# LSM9DS1.net
KiCad netlist of a schematic drawn in Altium Designer
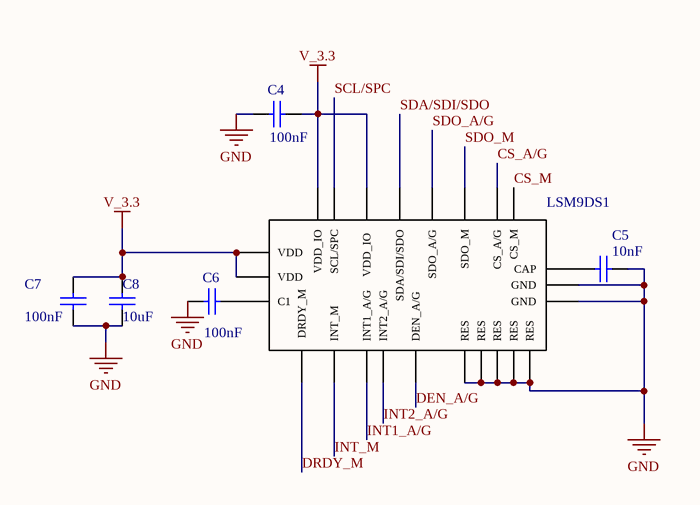
[diagram p0: LSM9DS1.SchDoc]

(export (version "E")
  (design (tool "Eeschema 10.0.6"))
  (components
    (comp (ref "C4")
      (value "100nF")
      (footprint "RAD-0.3")
      (description "Capacitor")
      (fields (field (name "Comment") "Cap") (field (name "PUBLISHER") "Altium Limited"))
      (libsource (lib "Miscellaneous Devices") (part "Cap"))
    )
    (comp (ref "C5")
      (value "10nF")
      (footprint "RAD-0.3")
      (description "Capacitor")
      (fields (field (name "Comment") "Cap") (field (name "PUBLISHER") "Altium Limited"))
      (libsource (lib "Miscellaneous Devices") (part "Cap"))
    )
    (comp (ref "C6")
      (value "100nF")
      (footprint "RAD-0.3")
      (description "Capacitor")
      (fields (field (name "Comment") "Cap") (field (name "PUBLISHER") "Altium Limited"))
      (libsource (lib "Miscellaneous Devices") (part "Cap"))
    )
    (comp (ref "C7")
      (value "100nF")
      (footprint "RAD-0.3")
      (description "Capacitor")
      (fields (field (name "Comment") "Cap") (field (name "PUBLISHER") "Altium Limited"))
      (libsource (lib "Miscellaneous Devices") (part "Cap"))
    )
    (comp (ref "C8")
      (value "10uF")
      (footprint "RAD-0.3")
      (description "Capacitor")
      (fields (field (name "Comment") "Cap") (field (name "PUBLISHER") "Altium Limited"))
      (libsource (lib "Miscellaneous Devices") (part "Cap"))
    )
    (comp (ref "LSM9DS1") (value "LSM9DS1") (libsource (lib "Schematic Components") (part "LSM9DS1")))
  )
  (nets
    (net (code "1") (name "/CS_A{slash}G") (class "Default")
      (node (ref "LSM9DS1") (pin "6") (pinfunction "CS_A/G_6") (pintype "passive"))
    )
    (net (code "2") (name "/CS_M") (class "Default")
      (node (ref "LSM9DS1") (pin "7") (pinfunction "CS_M_7") (pintype "passive"))
    )
    (net (code "3") (name "/DEN_A{slash}G") (class "Default")
      (node (ref "LSM9DS1") (pin "12") (pinfunction "DEN_A/G_12") (pintype "passive"))
    )
    (net (code "4") (name "/DRDY_M") (class "Default")
      (node (ref "LSM9DS1") (pin "8") (pinfunction "DRDY_M_8") (pintype "passive"))
    )
    (net (code "5") (name "/INT1_A{slash}G") (class "Default")
      (node (ref "LSM9DS1") (pin "10") (pinfunction "INT1_A/G_10") (pintype "passive"))
    )
    (net (code "6") (name "/INT2_A{slash}G") (class "Default")
      (node (ref "LSM9DS1") (pin "11") (pinfunction "INT2_A/G_11") (pintype "passive"))
    )
    (net (code "7") (name "/INT_M") (class "Default")
      (node (ref "LSM9DS1") (pin "9") (pinfunction "INT_M_9") (pintype "passive"))
    )
    (net (code "8") (name "/SCL{slash}SPC") (class "Default")
      (node (ref "LSM9DS1") (pin "1") (pinfunction "SCL/SPC_1") (pintype "passive"))
    )
    (net (code "9") (name "/SDA{slash}SDI{slash}SDO") (class "Default")
      (node (ref "LSM9DS1") (pin "3") (pinfunction "SDA/SDI/SDO_3") (pintype "passive"))
    )
    (net (code "10") (name "/SDO_A{slash}G") (class "Default")
      (node (ref "LSM9DS1") (pin "4") (pinfunction "SDO_A/G_4") (pintype "passive"))
    )
    (net (code "11") (name "/SDO_M") (class "Default")
      (node (ref "LSM9DS1") (pin "5") (pinfunction "SDO_M_5") (pintype "passive"))
    )
    (net (code "12") (name "GND") (class "Default")
      (node (ref "C4") (pin "1") (pinfunction "1_1") (pintype "passive"))
      (node (ref "C5") (pin "2") (pinfunction "2_2") (pintype "passive"))
      (node (ref "C6") (pin "1") (pinfunction "1_1") (pintype "passive"))
      (node (ref "C7") (pin "2") (pinfunction "2_2") (pintype "passive"))
      (node (ref "C8") (pin "2") (pinfunction "2_2") (pintype "passive"))
      (node (ref "LSM9DS1") (pin "13") (pinfunction "RES_13") (pintype "passive"))
      (node (ref "LSM9DS1") (pin "14") (pinfunction "RES_14") (pintype "passive"))
      (node (ref "LSM9DS1") (pin "15") (pinfunction "RES_15") (pintype "passive"))
      (node (ref "LSM9DS1") (pin "16") (pinfunction "RES_16") (pintype "passive"))
      (node (ref "LSM9DS1") (pin "17") (pinfunction "RES_17") (pintype "passive"))
      (node (ref "LSM9DS1") (pin "18") (pinfunction "GND_18") (pintype "passive"))
      (node (ref "LSM9DS1") (pin "19") (pinfunction "GND_19") (pintype "passive"))
    )
    (net (code "13") (name "Net-(LSM9DS1-C1)") (class "Default")
      (node (ref "C6") (pin "2") (pinfunction "2_2") (pintype "passive"))
      (node (ref "LSM9DS1") (pin "23") (pinfunction "C1_23") (pintype "passive"))
    )
    (net (code "14") (name "Net-(LSM9DS1-CAP)") (class "Default")
      (node (ref "C5") (pin "1") (pinfunction "1_1") (pintype "passive"))
      (node (ref "LSM9DS1") (pin "20") (pinfunction "CAP_20") (pintype "passive"))
    )
    (net (code "15") (name "V_3.3") (class "Default")
      (node (ref "C4") (pin "2") (pinfunction "2_2") (pintype "passive"))
      (node (ref "C7") (pin "1") (pinfunction "1_1") (pintype "passive"))
      (node (ref "C8") (pin "1") (pinfunction "1_1") (pintype "passive"))
      (node (ref "LSM9DS1") (pin "0") (pinfunction "VDD_IO_0") (pintype "passive"))
      (node (ref "LSM9DS1") (pin "2") (pinfunction "VDD_IO_2") (pintype "passive"))
      (node (ref "LSM9DS1") (pin "21") (pinfunction "VDD_21") (pintype "passive"))
      (node (ref "LSM9DS1") (pin "22") (pinfunction "VDD_22") (pintype "passive"))
    )
  )
)
